# skema.net
KiCad netlist of a schematic drawn in EAGLE
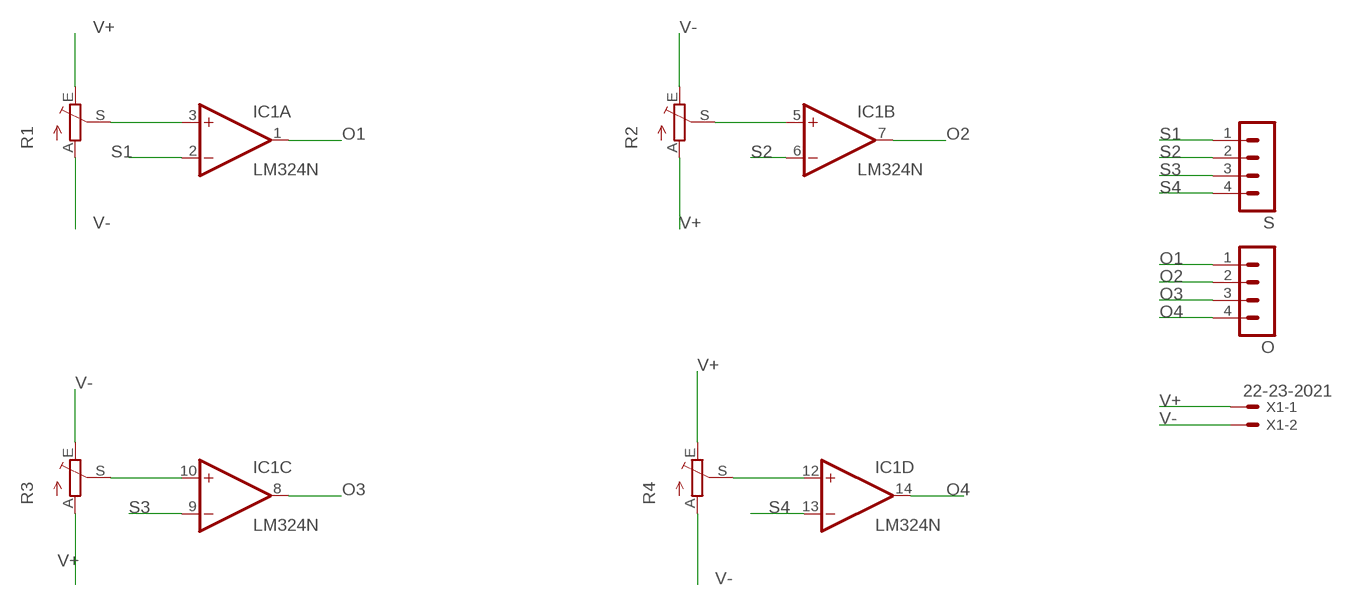
[diagram p0: schematic, sheet 1]

(export (version "E")
  (design (tool "Eeschema 10.0.6"))
  (components
    (comp (ref "IC1")
      (value "LM324N")
      (footprint "eagle-import:DIL14")
      (libsource (lib "eagle-import") (part "LM324N"))
    )
    (comp (ref "O")
      (value "MA04-1")
      (footprint "eagle-import:MA04-1")
      (libsource (lib "eagle-import") (part "MA04-1"))
    )
    (comp (ref "R1")
      (value "TRIM_EU-CA6V")
      (footprint "eagle-import:CA6V")
      (libsource (lib "eagle-import") (part "TRIM_EU-CA6V"))
    )
    (comp (ref "R2")
      (value "TRIM_EU-CA6V")
      (footprint "eagle-import:CA6V")
      (libsource (lib "eagle-import") (part "TRIM_EU-CA6V"))
    )
    (comp (ref "R3")
      (value "TRIM_EU-CA6V")
      (footprint "eagle-import:CA6V")
      (libsource (lib "eagle-import") (part "TRIM_EU-CA6V"))
    )
    (comp (ref "R4")
      (value "TRIM_EU-CA6V")
      (footprint "eagle-import:CA6V")
      (libsource (lib "eagle-import") (part "TRIM_EU-CA6V"))
    )
    (comp (ref "S")
      (value "MA04-1")
      (footprint "eagle-import:MA04-1")
      (libsource (lib "eagle-import") (part "MA04-1"))
    )
    (comp (ref "X1")
      (value "22-23-2021")
      (footprint "eagle-import:22-23-2021")
      (fields (field (name "MF") "MOLEX"))
      (libsource (lib "eagle-import") (part "22-23-2021"))
    )
  )
  (nets
    (net (code "1") (name "/O1") (class "Default")
      (node (ref "IC1") (pin "1") (pinfunction "OUT_1") (pintype "output"))
      (node (ref "O") (pin "1") (pinfunction "1_1") (pintype "passive"))
    )
    (net (code "2") (name "/O2") (class "Default")
      (node (ref "IC1") (pin "7") (pinfunction "OUT_7") (pintype "output"))
      (node (ref "O") (pin "2") (pinfunction "2_2") (pintype "passive"))
    )
    (net (code "3") (name "/O3") (class "Default")
      (node (ref "IC1") (pin "8") (pinfunction "OUT_8") (pintype "output"))
      (node (ref "O") (pin "3") (pinfunction "3_3") (pintype "passive"))
    )
    (net (code "4") (name "/O4") (class "Default")
      (node (ref "IC1") (pin "14") (pinfunction "OUT_14") (pintype "output"))
      (node (ref "O") (pin "4") (pinfunction "4_4") (pintype "passive"))
    )
    (net (code "5") (name "/S1") (class "Default")
      (node (ref "IC1") (pin "2") (pinfunction "-IN_2") (pintype "input"))
      (node (ref "S") (pin "1") (pinfunction "1_1") (pintype "passive"))
    )
    (net (code "6") (name "/S2") (class "Default")
      (node (ref "IC1") (pin "6") (pinfunction "-IN_6") (pintype "input"))
      (node (ref "S") (pin "2") (pinfunction "2_2") (pintype "passive"))
    )
    (net (code "7") (name "/S3") (class "Default")
      (node (ref "IC1") (pin "9") (pinfunction "-IN_9") (pintype "input"))
      (node (ref "S") (pin "3") (pinfunction "3_3") (pintype "passive"))
    )
    (net (code "8") (name "/S4") (class "Default")
      (node (ref "IC1") (pin "13") (pinfunction "-IN_13") (pintype "input"))
      (node (ref "S") (pin "4") (pinfunction "4_4") (pintype "passive"))
    )
    (net (code "9") (name "/V+") (class "Default")
      (node (ref "R1") (pin "E") (pinfunction "E_E") (pintype "passive"))
      (node (ref "R2") (pin "A") (pinfunction "A_A") (pintype "passive"))
      (node (ref "R3") (pin "A") (pinfunction "A_A") (pintype "passive"))
      (node (ref "R4") (pin "E") (pinfunction "E_E") (pintype "passive"))
      (node (ref "X1") (pin "1") (pinfunction "S_1") (pintype "passive"))
    )
    (net (code "10") (name "/V-") (class "Default")
      (node (ref "R1") (pin "A") (pinfunction "A_A") (pintype "passive"))
      (node (ref "R2") (pin "E") (pinfunction "E_E") (pintype "passive"))
      (node (ref "R3") (pin "E") (pinfunction "E_E") (pintype "passive"))
      (node (ref "R4") (pin "A") (pinfunction "A_A") (pintype "passive"))
      (node (ref "X1") (pin "2") (pinfunction "S_2") (pintype "passive"))
    )
    (net (code "11") (name "Net-(IC1A-+IN)") (class "Default")
      (node (ref "IC1") (pin "3") (pinfunction "+IN_3") (pintype "input"))
      (node (ref "R1") (pin "S") (pinfunction "S_S") (pintype "passive"))
    )
    (net (code "12") (name "Net-(IC1B-+IN)") (class "Default")
      (node (ref "IC1") (pin "5") (pinfunction "+IN_5") (pintype "input"))
      (node (ref "R2") (pin "S") (pinfunction "S_S") (pintype "passive"))
    )
    (net (code "13") (name "Net-(IC1C-+IN)") (class "Default")
      (node (ref "IC1") (pin "10") (pinfunction "+IN_10") (pintype "input"))
      (node (ref "R3") (pin "S") (pinfunction "S_S") (pintype "passive"))
    )
    (net (code "14") (name "Net-(IC1D-+IN)") (class "Default")
      (node (ref "IC1") (pin "12") (pinfunction "+IN_12") (pintype "input"))
      (node (ref "R4") (pin "S") (pinfunction "S_S") (pintype "passive"))
    )
  )
)
